# NwazetPowerSwitchModule.net
KiCad netlist of a schematic drawn in EAGLE
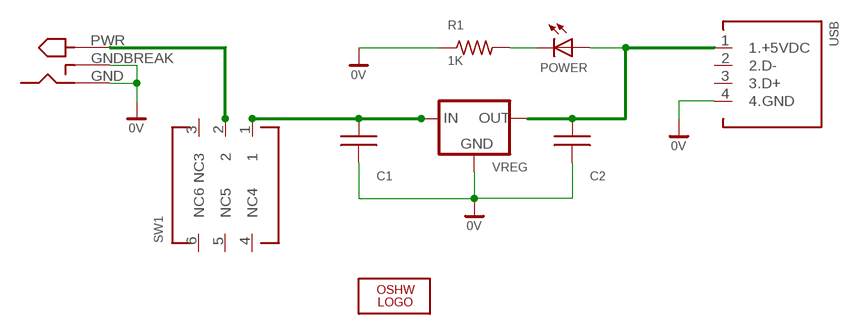
[diagram p0: schematic, sheet 1]

(export (version "E")
  (design (tool "Eeschema 10.0.6"))
  (components
    (comp (ref "C1")
      (value "0.47uF")
      (footprint "eagle-import:0805")
      (libsource (lib "eagle-import") (part "CAP_CER_2.2UF_0805"))
    )
    (comp (ref "C2")
      (value "MURATA_GRM_10UF_CER_0805")
      (footprint "eagle-import:0805")
      (libsource (lib "eagle-import") (part "MURATA_GRM_10UF_CER_0805"))
    )
    (comp (ref "LOGO1")
      (value "OSHW_LOGO_FILLX0100-NT")
      (footprint "eagle-import:OSHW_FILLX100_NOTEXT")
      (libsource (lib "eagle-import") (part "OSHW_LOGO_FILLX0100-NT"))
    )
    (comp (ref "PJ")
      (value "CUI_POWER_JACK_102A")
      (footprint "eagle-import:CUI_PJ-102A")
      (libsource (lib "eagle-import") (part "CUI_POWER_JACK_102A"))
    )
    (comp (ref "POWER")
      (value "LITEON_WHITE_LED_0805")
      (footprint "eagle-import:0805")
      (libsource (lib "eagle-import") (part "LITEON_WHITE_LED_0805"))
    )
    (comp (ref "R1")
      (value "1K")
      (footprint "eagle-import:0805")
      (libsource (lib "eagle-import") (part "RESISTOR_0805"))
    )
    (comp (ref "SW1")
      (value "CTS_065T_SPST_SLIDE_SWITCH")
      (footprint "eagle-import:CTS_065T_SPST_SLIDE_SWITCH")
      (libsource (lib "eagle-import") (part "CTS_065T_SPST_SLIDE_SWITCH"))
    )
    (comp (ref "USB")
      (value "AMPHENOL_USB_TYPE_A_FEMALE_CONNECTOR")
      (footprint "eagle-import:USB_CONNECTOR_TYPE_A_FEMALE")
      (libsource (lib "eagle-import") (part "AMPHENOL_USB_TYPE_A_FEMALE_CONNECTOR"))
    )
    (comp (ref "VREG")
      (value "ON_MC33269_800MA_VREG")
      (footprint "eagle-import:800MA_VREG_DPAK")
      (libsource (lib "eagle-import") (part "ON_MC33269_800MA_VREG"))
    )
  )
  (nets
    (net (code "1") (name "0V") (class "Default")
      (node (ref "C1") (pin "A") (pinfunction "1_A") (pintype "passive"))
      (node (ref "C2") (pin "A") (pinfunction "1_A") (pintype "passive"))
      (node (ref "PJ") (pin "GND") (pinfunction "GND_GND") (pintype "passive"))
      (node (ref "PJ") (pin "GNDBREAK") (pinfunction "GNDBREAK_GNDBREAK") (pintype "passive"))
      (node (ref "R1") (pin "A") (pinfunction "1_A") (pintype "passive"))
      (node (ref "USB") (pin "4") (pinfunction "4.GND_4") (pintype "passive"))
      (node (ref "VREG") (pin "1.GND_ADJ") (pinfunction "GND_1.GND_ADJ") (pintype "passive"))
    )
    (net (code "2") (name "Net-(C1-2)") (class "Default")
      (node (ref "C1") (pin "K") (pinfunction "2_K") (pintype "passive"))
      (node (ref "SW1") (pin "1") (pinfunction "1_1") (pintype "passive"))
      (node (ref "VREG") (pin "3.VIN") (pinfunction "IN_3.VIN") (pintype "power_in"))
    )
    (net (code "3") (name "Net-(C2-2)") (class "Default")
      (node (ref "C2") (pin "K") (pinfunction "2_K") (pintype "passive"))
      (node (ref "POWER") (pin "A") (pinfunction "A_A") (pintype "passive"))
      (node (ref "USB") (pin "1") (pinfunction "1.+5VDC_1") (pintype "power_in"))
      (node (ref "VREG") (pin "2.VOUT") (pinfunction "OUT_2.VOUT") (pintype "output"))
    )
    (net (code "4") (name "Net-(PJ-PadPWR)") (class "Default")
      (node (ref "PJ") (pin "PWR") (pinfunction "PWR_PWR") (pintype "power_in"))
      (node (ref "SW1") (pin "2") (pinfunction "2_2") (pintype "passive"))
    )
    (net (code "5") (name "Net-(POWER-C)") (class "Default")
      (node (ref "POWER") (pin "K") (pinfunction "C_K") (pintype "passive"))
      (node (ref "R1") (pin "K") (pinfunction "2_K") (pintype "passive"))
    )
    (net (code "6") (name "unconnected-(SW1-NC3-Pad3)") (class "Default")
      (node (ref "SW1") (pin "3") (pinfunction "NC3_3") (pintype "passive"))
    )
    (net (code "7") (name "unconnected-(SW1-NC4-Pad4)") (class "Default")
      (node (ref "SW1") (pin "4") (pinfunction "NC4_4") (pintype "passive"))
    )
    (net (code "8") (name "unconnected-(SW1-NC5-Pad5)") (class "Default")
      (node (ref "SW1") (pin "5") (pinfunction "NC5_5") (pintype "passive"))
    )
    (net (code "9") (name "unconnected-(SW1-NC6-Pad6)") (class "Default")
      (node (ref "SW1") (pin "6") (pinfunction "NC6_6") (pintype "passive"))
    )
    (net (code "10") (name "unconnected-(USB-2.D--Pad2)") (class "Default")
      (node (ref "USB") (pin "2") (pinfunction "2.D-_2") (pintype "bidirectional"))
    )
    (net (code "11") (name "unconnected-(USB-3.D+-Pad3)") (class "Default")
      (node (ref "USB") (pin "3") (pinfunction "3.D+_3") (pintype "bidirectional"))
    )
  )
)
